# Processor.net
KiCad netlist of a schematic drawn in Altium Designer
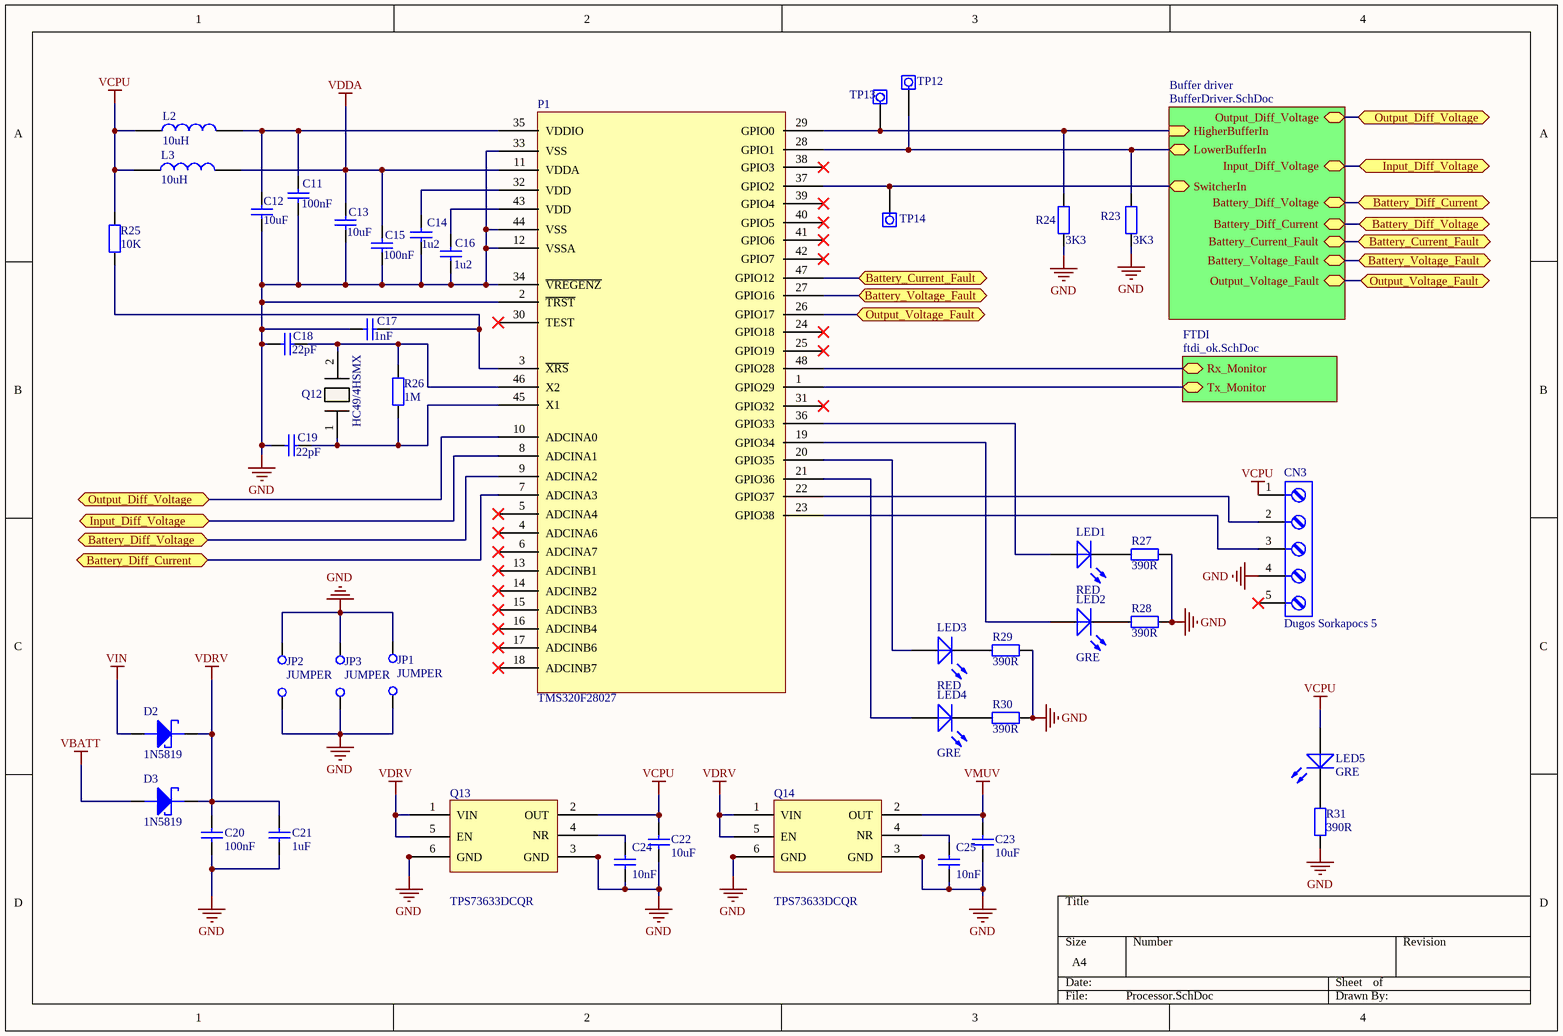
[diagram p0: Processor.SchDoc]

(export (version "E")
  (design (tool "Eeschema 10.0.6"))
  (components
    (comp (ref "C11")
      (value "100nF")
      (footprint "FP_0805_CAP_085")
      (description "Capacitor")
      (libsource (lib "hallglib") (part "CAP"))
    )
    (comp (ref "C12")
      (value "10uF")
      (footprint "FP_0805_CAP_085")
      (description "Capacitor")
      (libsource (lib "hallglib") (part "CAP"))
    )
    (comp (ref "C13")
      (value "10uF")
      (footprint "FP_0805_CAP_085")
      (description "Capacitor")
      (libsource (lib "hallglib") (part "CAP"))
    )
    (comp (ref "C14")
      (value "1u2")
      (footprint "FP_1206_CAP_125")
      (description "Capacitor")
      (libsource (lib "hallglib") (part "CAP"))
    )
    (comp (ref "C15")
      (value "100nF")
      (footprint "FP_0805_CAP_085")
      (description "Capacitor")
      (libsource (lib "hallglib") (part "CAP"))
    )
    (comp (ref "C16")
      (value "1u2")
      (footprint "FP_1206_CAP_125")
      (description "Capacitor")
      (libsource (lib "hallglib") (part "CAP"))
    )
    (comp (ref "C17")
      (value "1nF")
      (footprint "FP_0805_CAP_085")
      (description "Capacitor")
      (libsource (lib "hallglib") (part "CAP"))
    )
    (comp (ref "C18")
      (value "22pF")
      (footprint "FP_0805_CAP_085")
      (description "Capacitor")
      (libsource (lib "hallglib") (part "CAP"))
    )
    (comp (ref "C19")
      (value "22pF")
      (footprint "FP_0805_CAP_085")
      (description "Capacitor")
      (libsource (lib "hallglib") (part "CAP"))
    )
    (comp (ref "C20")
      (value "100nF")
      (footprint "FP_0805_CAP_085")
      (description "Capacitor")
      (libsource (lib "hallglib") (part "CAP"))
    )
    (comp (ref "C21")
      (value "1uF")
      (footprint "FP_0805_CAP_085")
      (description "Capacitor")
      (libsource (lib "hallglib") (part "CAP"))
    )
    (comp (ref "C22")
      (value "10uF")
      (footprint "FP_0805_CAP_085")
      (description "Capacitor")
      (libsource (lib "hallglib") (part "CAP"))
    )
    (comp (ref "C23")
      (value "10uF")
      (footprint "FP_0805_CAP_085")
      (description "Capacitor")
      (libsource (lib "hallglib") (part "CAP"))
    )
    (comp (ref "C24")
      (value "10nF")
      (footprint "FP_0805_CAP_085")
      (description "Capacitor")
      (libsource (lib "hallglib") (part "CAP"))
    )
    (comp (ref "C25")
      (value "10nF")
      (footprint "FP_0805_CAP_085")
      (description "Capacitor")
      (libsource (lib "hallglib") (part "CAP"))
    )
    (comp (ref "CN3")
      (value "Dugos Sorkapocs 5")
      (footprint "FP_CONN4_TUSKE_254MM")
      (description "SORKAPOCS 5 P RM5.08 CSAPSORLÉC 90° ZÁRT 12A")
      (libsource (lib "MERES") (part "Dugos Sorkapocs 5"))
    )
    (comp (ref "D2")
      (value "1N5819")
      (footprint "AXIAL-0.3")
      (description "NXP - PMEG3020EJ,115 - SCHOTTKY RECT 30V 2A SOD323F")
      (libsource (lib "hallglib") (part "SCHOTTKY"))
    )
    (comp (ref "D3")
      (value "1N5819")
      (footprint "AXIAL-0.3")
      (description "NXP - PMEG3020EJ,115 - SCHOTTKY RECT 30V 2A SOD323F")
      (libsource (lib "hallglib") (part "SCHOTTKY"))
    )
    (comp (ref "JP1")
      (value "JUMPER")
      (footprint "FP_CONN2_TUSKE_254MM")
      (description "Jumper Wire")
      (libsource (lib "hallglib") (part "JUMPER"))
    )
    (comp (ref "JP2")
      (value "JUMPER")
      (footprint "FP_CONN2_TUSKE_254MM")
      (description "Jumper Wire")
      (libsource (lib "hallglib") (part "JUMPER"))
    )
    (comp (ref "JP3")
      (value "JUMPER")
      (footprint "FP_CONN2_TUSKE_254MM")
      (description "Jumper Wire")
      (libsource (lib "hallglib") (part "JUMPER"))
    )
    (comp (ref "L2")
      (value "10uH")
      (footprint "AXIAL-0.3")
      (description "Inductor")
      (libsource (lib "hallglib") (part "IND"))
    )
    (comp (ref "L3")
      (value "10uH")
      (footprint "AXIAL-0.3")
      (description "Inductor")
      (libsource (lib "hallglib") (part "IND"))
    )
    (comp (ref "LED1")
      (value "RED")
      (footprint "FP_LED_TH_RED")
      (description "LED")
      (libsource (lib "hallglib") (part "LED"))
    )
    (comp (ref "LED2")
      (value "GRE")
      (footprint "FP_LED_TH_GREEN")
      (description "LED")
      (libsource (lib "hallglib") (part "LED"))
    )
    (comp (ref "LED3")
      (value "RED")
      (footprint "FP_LED_TH_RED")
      (description "LED")
      (libsource (lib "hallglib") (part "LED"))
    )
    (comp (ref "LED4")
      (value "GRE")
      (footprint "FP_LED_TH_GREEN")
      (description "LED")
      (libsource (lib "hallglib") (part "LED"))
    )
    (comp (ref "LED5")
      (value "GRE")
      (footprint "FP_LED_TH_GREEN")
      (description "LED")
      (libsource (lib "hallglib") (part "LED"))
    )
    (comp (ref "P1")
      (value "TMS320F28027")
      (footprint "S-PQFP48")
      (description "Processor")
      (libsource (lib "hallglib") (part "TMS320F28027"))
    )
    (comp (ref "Q12")
      (value "HC49/4HSMX")
      (footprint "Crystal_10MHz")
      (description "kristály")
      (libsource (lib "hallglib") (part "HC49/4HSMX"))
    )
    (comp (ref "Q13")
      (value "TPS73633DCQR")
      (footprint "TPS73633")
      (description "proci táp 3V3")
      (libsource (lib "hallglib") (part "TPS73633DCQR"))
    )
    (comp (ref "Q14")
      (value "TPS73633DCQR")
      (footprint "TPS73633")
      (description "proci táp 3V3")
      (libsource (lib "hallglib") (part "TPS73633DCQR"))
    )
    (comp (ref "R23")
      (value "3K3")
      (footprint "FP_0805_RES")
      (description "Resistor")
      (libsource (lib "") (part "RES_1"))
    )
    (comp (ref "R24")
      (value "3K3")
      (footprint "FP_0805_RES")
      (description "Resistor")
      (libsource (lib "hallglib") (part "RES"))
    )
    (comp (ref "R25")
      (value "10K")
      (footprint "FP_0805_RES")
      (description "Resistor")
      (libsource (lib "hallglib") (part "RES"))
    )
    (comp (ref "R26")
      (value "1M")
      (footprint "FP_0805_RES")
      (description "Resistor")
      (libsource (lib "hallglib") (part "RES"))
    )
    (comp (ref "R27") (value "390R") (footprint "AXIAL-0.3") (libsource (lib "") (part "Resistor_1")))
    (comp (ref "R28") (value "390R") (footprint "AXIAL-0.3") (libsource (lib "") (part "Resistor_1")))
    (comp (ref "R29") (value "390R") (footprint "AXIAL-0.3") (libsource (lib "") (part "Resistor_1")))
    (comp (ref "R30") (value "390R") (footprint "AXIAL-0.3") (libsource (lib "") (part "Resistor_1")))
    (comp (ref "R31") (value "390R") (footprint "AXIAL-0.3") (libsource (lib "hallglib") (part "Resistor")))
    (comp (ref "TP12")
      (value "Testpoint")
      (footprint "TESTPOINT_1.5")
      (libsource (lib "MERES") (part "Testpoint"))
    )
    (comp (ref "TP13")
      (value "Testpoint")
      (footprint "TESTPOINT_1.5")
      (libsource (lib "MERES") (part "Testpoint"))
    )
    (comp (ref "TP14")
      (value "Testpoint")
      (footprint "TESTPOINT_1.5")
      (libsource (lib "MERES") (part "Testpoint"))
    )
  )
  (nets
    (net (code "1") (name "/Battery_Current_Fault") (class "Default")
      (node (ref "P1") (pin "47") (pinfunction "GPIO12_47") (pintype "passive"))
    )
    (net (code "2") (name "/Battery_Diff_Current") (class "Default")
      (node (ref "P1") (pin "7") (pinfunction "ADCINA3_7") (pintype "passive"))
    )
    (net (code "3") (name "/Battery_Diff_Voltage") (class "Default")
      (node (ref "P1") (pin "9") (pinfunction "ADCINA2_9") (pintype "passive"))
    )
    (net (code "4") (name "/Battery_Voltage_Fault") (class "Default")
      (node (ref "P1") (pin "27") (pinfunction "GPIO16_27") (pintype "passive"))
    )
    (net (code "5") (name "/HigherBufferIn") (class "Default")
      (node (ref "P1") (pin "29") (pinfunction "GPIO0_29") (pintype "passive"))
      (node (ref "R24") (pin "2") (pinfunction "2_2") (pintype "passive"))
      (node (ref "TP13") (pin "1") (pinfunction "1_1") (pintype "passive"))
    )
    (net (code "6") (name "/Input_Diff_Voltage") (class "Default")
      (node (ref "P1") (pin "8") (pinfunction "ADCINA1_8") (pintype "passive"))
    )
    (net (code "7") (name "/LowerBufferIn") (class "Default")
      (node (ref "P1") (pin "28") (pinfunction "GPIO1_28") (pintype "passive"))
      (node (ref "R23") (pin "1") (pinfunction "1_1") (pintype "passive"))
      (node (ref "TP12") (pin "1") (pinfunction "1_1") (pintype "passive"))
    )
    (net (code "8") (name "/Output_Diff_Voltage") (class "Default")
      (node (ref "P1") (pin "10") (pinfunction "ADCINA0_10") (pintype "passive"))
    )
    (net (code "9") (name "/Output_Voltage_Fault") (class "Default")
      (node (ref "P1") (pin "26") (pinfunction "GPIO17_26") (pintype "passive"))
    )
    (net (code "10") (name "/Rx_Monitor") (class "Default")
      (node (ref "P1") (pin "48") (pinfunction "GPIO28_48") (pintype "passive"))
    )
    (net (code "11") (name "/SwitcherIn") (class "Default")
      (node (ref "P1") (pin "37") (pinfunction "GPIO2_37") (pintype "passive"))
      (node (ref "TP14") (pin "1") (pinfunction "1_1") (pintype "passive"))
    )
    (net (code "12") (name "/Tx_Monitor") (class "Default")
      (node (ref "P1") (pin "1") (pinfunction "GPIO29_1") (pintype "passive"))
    )
    (net (code "13") (name "GND") (class "Default")
      (node (ref "C11") (pin "1") (pinfunction "1_1") (pintype "passive"))
      (node (ref "C12") (pin "1") (pinfunction "1_1") (pintype "passive"))
      (node (ref "C13") (pin "1") (pinfunction "1_1") (pintype "passive"))
      (node (ref "C14") (pin "1") (pinfunction "1_1") (pintype "passive"))
      (node (ref "C15") (pin "2") (pinfunction "2_2") (pintype "passive"))
      (node (ref "C16") (pin "1") (pinfunction "1_1") (pintype "passive"))
      (node (ref "C17") (pin "1") (pinfunction "1_1") (pintype "passive"))
      (node (ref "C18") (pin "1") (pinfunction "1_1") (pintype "passive"))
      (node (ref "C19") (pin "1") (pinfunction "1_1") (pintype "passive"))
      (node (ref "C20") (pin "1") (pinfunction "1_1") (pintype "passive"))
      (node (ref "C21") (pin "1") (pinfunction "1_1") (pintype "passive"))
      (node (ref "C22") (pin "1") (pinfunction "1_1") (pintype "passive"))
      (node (ref "C23") (pin "1") (pinfunction "1_1") (pintype "passive"))
      (node (ref "C24") (pin "1") (pinfunction "1_1") (pintype "passive"))
      (node (ref "C25") (pin "1") (pinfunction "1_1") (pintype "passive"))
      (node (ref "CN3") (pin "4") (pinfunction "4_4") (pintype "passive"))
      (node (ref "JP1") (pin "1") (pinfunction "C1_1") (pintype "passive"))
      (node (ref "JP1") (pin "2") (pinfunction "C2_2") (pintype "passive"))
      (node (ref "JP2") (pin "1") (pinfunction "C1_1") (pintype "passive"))
      (node (ref "JP2") (pin "2") (pinfunction "C2_2") (pintype "passive"))
      (node (ref "JP3") (pin "1") (pinfunction "C1_1") (pintype "passive"))
      (node (ref "JP3") (pin "2") (pinfunction "C2_2") (pintype "passive"))
      (node (ref "P1") (pin "12") (pinfunction "VSSA_12") (pintype "passive"))
      (node (ref "P1") (pin "2") (pinfunction "~{TRST}_2") (pintype "passive"))
      (node (ref "P1") (pin "33") (pinfunction "VSS_33") (pintype "passive"))
      (node (ref "P1") (pin "34") (pinfunction "~{VREGENZ}_34") (pintype "passive"))
      (node (ref "P1") (pin "44") (pinfunction "VSS_44") (pintype "passive"))
      (node (ref "Q13") (pin "3") (pinfunction "GND_3") (pintype "passive"))
      (node (ref "Q13") (pin "6") (pinfunction "GND_6") (pintype "passive"))
      (node (ref "Q14") (pin "3") (pinfunction "GND_3") (pintype "passive"))
      (node (ref "Q14") (pin "6") (pinfunction "GND_6") (pintype "passive"))
      (node (ref "R23") (pin "2") (pinfunction "2_2") (pintype "passive"))
      (node (ref "R24") (pin "1") (pinfunction "1_1") (pintype "passive"))
      (node (ref "R27") (pin "1") (pinfunction "1_1") (pintype "passive"))
      (node (ref "R28") (pin "1") (pinfunction "1_1") (pintype "passive"))
      (node (ref "R29") (pin "1") (pinfunction "1_1") (pintype "passive"))
      (node (ref "R30") (pin "1") (pinfunction "1_1") (pintype "passive"))
      (node (ref "R31") (pin "1") (pinfunction "1_1") (pintype "passive"))
    )
    (net (code "14") (name "Net-(C14-Pad2)") (class "Default")
      (node (ref "C14") (pin "2") (pinfunction "2_2") (pintype "passive"))
      (node (ref "P1") (pin "32") (pinfunction "VDD_32") (pintype "passive"))
    )
    (net (code "15") (name "Net-(C16-Pad2)") (class "Default")
      (node (ref "C16") (pin "2") (pinfunction "2_2") (pintype "passive"))
      (node (ref "P1") (pin "43") (pinfunction "VDD_43") (pintype "passive"))
    )
    (net (code "16") (name "Net-(LED1-A)") (class "Default")
      (node (ref "LED1") (pin "1") (pinfunction "A_1") (pintype "passive"))
      (node (ref "P1") (pin "36") (pinfunction "GPIO33_36") (pintype "passive"))
    )
    (net (code "17") (name "Net-(LED1-K)") (class "Default")
      (node (ref "LED1") (pin "2") (pinfunction "K_2") (pintype "passive"))
      (node (ref "R27") (pin "2") (pinfunction "2_2") (pintype "passive"))
    )
    (net (code "18") (name "Net-(LED2-A)") (class "Default")
      (node (ref "LED2") (pin "1") (pinfunction "A_1") (pintype "passive"))
      (node (ref "P1") (pin "19") (pinfunction "GPIO34_19") (pintype "passive"))
    )
    (net (code "19") (name "Net-(LED2-K)") (class "Default")
      (node (ref "LED2") (pin "2") (pinfunction "K_2") (pintype "passive"))
      (node (ref "R28") (pin "2") (pinfunction "2_2") (pintype "passive"))
    )
    (net (code "20") (name "Net-(LED3-A)") (class "Default")
      (node (ref "LED3") (pin "1") (pinfunction "A_1") (pintype "passive"))
      (node (ref "P1") (pin "20") (pinfunction "GPIO35_20") (pintype "passive"))
    )
    (net (code "21") (name "Net-(LED3-K)") (class "Default")
      (node (ref "LED3") (pin "2") (pinfunction "K_2") (pintype "passive"))
      (node (ref "R29") (pin "2") (pinfunction "2_2") (pintype "passive"))
    )
    (net (code "22") (name "Net-(LED4-A)") (class "Default")
      (node (ref "LED4") (pin "1") (pinfunction "A_1") (pintype "passive"))
      (node (ref "P1") (pin "21") (pinfunction "GPIO36_21") (pintype "passive"))
    )
    (net (code "23") (name "Net-(LED4-K)") (class "Default")
      (node (ref "LED4") (pin "2") (pinfunction "K_2") (pintype "passive"))
      (node (ref "R30") (pin "2") (pinfunction "2_2") (pintype "passive"))
    )
    (net (code "24") (name "Net-(LED5-K)") (class "Default")
      (node (ref "LED5") (pin "2") (pinfunction "K_2") (pintype "passive"))
      (node (ref "R31") (pin "2") (pinfunction "2_2") (pintype "passive"))
    )
    (net (code "25") (name "Net-(P1-GPIO37)") (class "Default")
      (node (ref "CN3") (pin "2") (pinfunction "2_2") (pintype "passive"))
      (node (ref "P1") (pin "22") (pinfunction "GPIO37_22") (pintype "passive"))
    )
    (net (code "26") (name "Net-(P1-GPIO38)") (class "Default")
      (node (ref "CN3") (pin "3") (pinfunction "3_3") (pintype "passive"))
      (node (ref "P1") (pin "23") (pinfunction "GPIO38_23") (pintype "passive"))
    )
    (net (code "27") (name "Net-(P1-VDDIO)") (class "Default")
      (node (ref "C11") (pin "2") (pinfunction "2_2") (pintype "passive"))
      (node (ref "C12") (pin "2") (pinfunction "2_2") (pintype "passive"))
      (node (ref "L2") (pin "2") (pinfunction "2_2") (pintype "passive"))
      (node (ref "P1") (pin "35") (pinfunction "VDDIO_35") (pintype "passive"))
    )
    (net (code "28") (name "Net-(P1-X1)") (class "Default")
      (node (ref "C19") (pin "2") (pinfunction "2_2") (pintype "passive"))
      (node (ref "P1") (pin "45") (pinfunction "X1_45") (pintype "passive"))
      (node (ref "Q12") (pin "1") (pinfunction "X1_1") (pintype "passive"))
      (node (ref "R26") (pin "1") (pinfunction "1_1") (pintype "passive"))
    )
    (net (code "29") (name "Net-(P1-X2)") (class "Default")
      (node (ref "C18") (pin "2") (pinfunction "2_2") (pintype "passive"))
      (node (ref "P1") (pin "46") (pinfunction "X2_46") (pintype "passive"))
      (node (ref "Q12") (pin "2") (pinfunction "X2_2") (pintype "passive"))
      (node (ref "R26") (pin "2") (pinfunction "2_2") (pintype "passive"))
    )
    (net (code "30") (name "Net-(P1-~{XRS})") (class "Default")
      (node (ref "C17") (pin "2") (pinfunction "2_2") (pintype "passive"))
      (node (ref "P1") (pin "3") (pinfunction "~{XRS}_3") (pintype "passive"))
      (node (ref "R25") (pin "1") (pinfunction "1_1") (pintype "passive"))
    )
    (net (code "31") (name "Net-(Q13-NR)") (class "Default")
      (node (ref "C24") (pin "2") (pinfunction "2_2") (pintype "passive"))
      (node (ref "Q13") (pin "4") (pinfunction "NR_4") (pintype "passive"))
    )
    (net (code "32") (name "Net-(Q14-NR)") (class "Default")
      (node (ref "C25") (pin "2") (pinfunction "2_2") (pintype "passive"))
      (node (ref "Q14") (pin "4") (pinfunction "NR_4") (pintype "passive"))
    )
    (net (code "33") (name "VBATT") (class "Default")
      (node (ref "D3") (pin "2") (pinfunction "ANODE_2") (pintype "passive"))
    )
    (net (code "34") (name "VCPU") (class "Default")
      (node (ref "C22") (pin "2") (pinfunction "2_2") (pintype "passive"))
      (node (ref "CN3") (pin "1") (pinfunction "1_1") (pintype "passive"))
      (node (ref "L2") (pin "1") (pinfunction "1_1") (pintype "passive"))
      (node (ref "L3") (pin "1") (pinfunction "1_1") (pintype "passive"))
      (node (ref "LED5") (pin "1") (pinfunction "A_1") (pintype "passive"))
      (node (ref "Q13") (pin "2") (pinfunction "OUT_2") (pintype "passive"))
      (node (ref "R25") (pin "2") (pinfunction "2_2") (pintype "passive"))
    )
    (net (code "35") (name "VDDA") (class "Default")
      (node (ref "C13") (pin "2") (pinfunction "2_2") (pintype "passive"))
      (node (ref "C15") (pin "1") (pinfunction "1_1") (pintype "passive"))
      (node (ref "L3") (pin "2") (pinfunction "2_2") (pintype "passive"))
      (node (ref "P1") (pin "11") (pinfunction "VDDA_11") (pintype "passive"))
    )
    (net (code "36") (name "VDRV") (class "Default")
      (node (ref "C20") (pin "2") (pinfunction "2_2") (pintype "passive"))
      (node (ref "C21") (pin "2") (pinfunction "2_2") (pintype "passive"))
      (node (ref "D2") (pin "1") (pinfunction "CATHODE_1") (pintype "passive"))
      (node (ref "D3") (pin "1") (pinfunction "CATHODE_1") (pintype "passive"))
      (node (ref "Q13") (pin "1") (pinfunction "VIN_1") (pintype "passive"))
      (node (ref "Q13") (pin "5") (pinfunction "EN_5") (pintype "passive"))
      (node (ref "Q14") (pin "1") (pinfunction "VIN_1") (pintype "passive"))
      (node (ref "Q14") (pin "5") (pinfunction "EN_5") (pintype "passive"))
    )
    (net (code "37") (name "VIN") (class "Default")
      (node (ref "D2") (pin "2") (pinfunction "ANODE_2") (pintype "passive"))
    )
    (net (code "38") (name "VMUV") (class "Default")
      (node (ref "C23") (pin "2") (pinfunction "2_2") (pintype "passive"))
      (node (ref "Q14") (pin "2") (pinfunction "OUT_2") (pintype "passive"))
    )
    (net (code "39") (name "unconnected-(CN3-Pad5)") (class "Default")
      (node (ref "CN3") (pin "5") (pinfunction "5_5") (pintype "passive+no_connect"))
    )
    (net (code "40") (name "unconnected-(P1-ADCINA4-Pad5)") (class "Default")
      (node (ref "P1") (pin "5") (pinfunction "ADCINA4_5") (pintype "passive+no_connect"))
    )
    (net (code "41") (name "unconnected-(P1-ADCINA6-Pad4)") (class "Default")
      (node (ref "P1") (pin "4") (pinfunction "ADCINA6_4") (pintype "passive+no_connect"))
    )
    (net (code "42") (name "unconnected-(P1-ADCINA7-Pad6)") (class "Default")
      (node (ref "P1") (pin "6") (pinfunction "ADCINA7_6") (pintype "passive+no_connect"))
    )
    (net (code "43") (name "unconnected-(P1-ADCINB1-Pad13)") (class "Default")
      (node (ref "P1") (pin "13") (pinfunction "ADCINB1_13") (pintype "passive+no_connect"))
    )
    (net (code "44") (name "unconnected-(P1-ADCINB2-Pad14)") (class "Default")
      (node (ref "P1") (pin "14") (pinfunction "ADCINB2_14") (pintype "passive+no_connect"))
    )
    (net (code "45") (name "unconnected-(P1-ADCINB3-Pad15)") (class "Default")
      (node (ref "P1") (pin "15") (pinfunction "ADCINB3_15") (pintype "passive+no_connect"))
    )
    (net (code "46") (name "unconnected-(P1-ADCINB4-Pad16)") (class "Default")
      (node (ref "P1") (pin "16") (pinfunction "ADCINB4_16") (pintype "passive+no_connect"))
    )
    (net (code "47") (name "unconnected-(P1-ADCINB6-Pad17)") (class "Default")
      (node (ref "P1") (pin "17") (pinfunction "ADCINB6_17") (pintype "passive+no_connect"))
    )
    (net (code "48") (name "unconnected-(P1-ADCINB7-Pad18)") (class "Default")
      (node (ref "P1") (pin "18") (pinfunction "ADCINB7_18") (pintype "passive+no_connect"))
    )
    (net (code "49") (name "unconnected-(P1-GPIO3-Pad38)") (class "Default")
      (node (ref "P1") (pin "38") (pinfunction "GPIO3_38") (pintype "passive+no_connect"))
    )
    (net (code "50") (name "unconnected-(P1-GPIO4-Pad39)") (class "Default")
      (node (ref "P1") (pin "39") (pinfunction "GPIO4_39") (pintype "passive+no_connect"))
    )
    (net (code "51") (name "unconnected-(P1-GPIO5-Pad40)") (class "Default")
      (node (ref "P1") (pin "40") (pinfunction "GPIO5_40") (pintype "passive+no_connect"))
    )
    (net (code "52") (name "unconnected-(P1-GPIO6-Pad41)") (class "Default")
      (node (ref "P1") (pin "41") (pinfunction "GPIO6_41") (pintype "passive+no_connect"))
    )
    (net (code "53") (name "unconnected-(P1-GPIO7-Pad42)") (class "Default")
      (node (ref "P1") (pin "42") (pinfunction "GPIO7_42") (pintype "passive+no_connect"))
    )
    (net (code "54") (name "unconnected-(P1-GPIO18-Pad24)") (class "Default")
      (node (ref "P1") (pin "24") (pinfunction "GPIO18_24") (pintype "passive+no_connect"))
    )
    (net (code "55") (name "unconnected-(P1-GPIO19-Pad25)") (class "Default")
      (node (ref "P1") (pin "25") (pinfunction "GPIO19_25") (pintype "passive+no_connect"))
    )
    (net (code "56") (name "unconnected-(P1-GPIO32-Pad31)") (class "Default")
      (node (ref "P1") (pin "31") (pinfunction "GPIO32_31") (pintype "passive+no_connect"))
    )
    (net (code "57") (name "unconnected-(P1-TEST-Pad30)") (class "Default")
      (node (ref "P1") (pin "30") (pinfunction "TEST_30") (pintype "passive+no_connect"))
    )
  )
)
